# ATX_Power_Breakout_v1p6.net
KiCad netlist of a schematic drawn in EAGLE
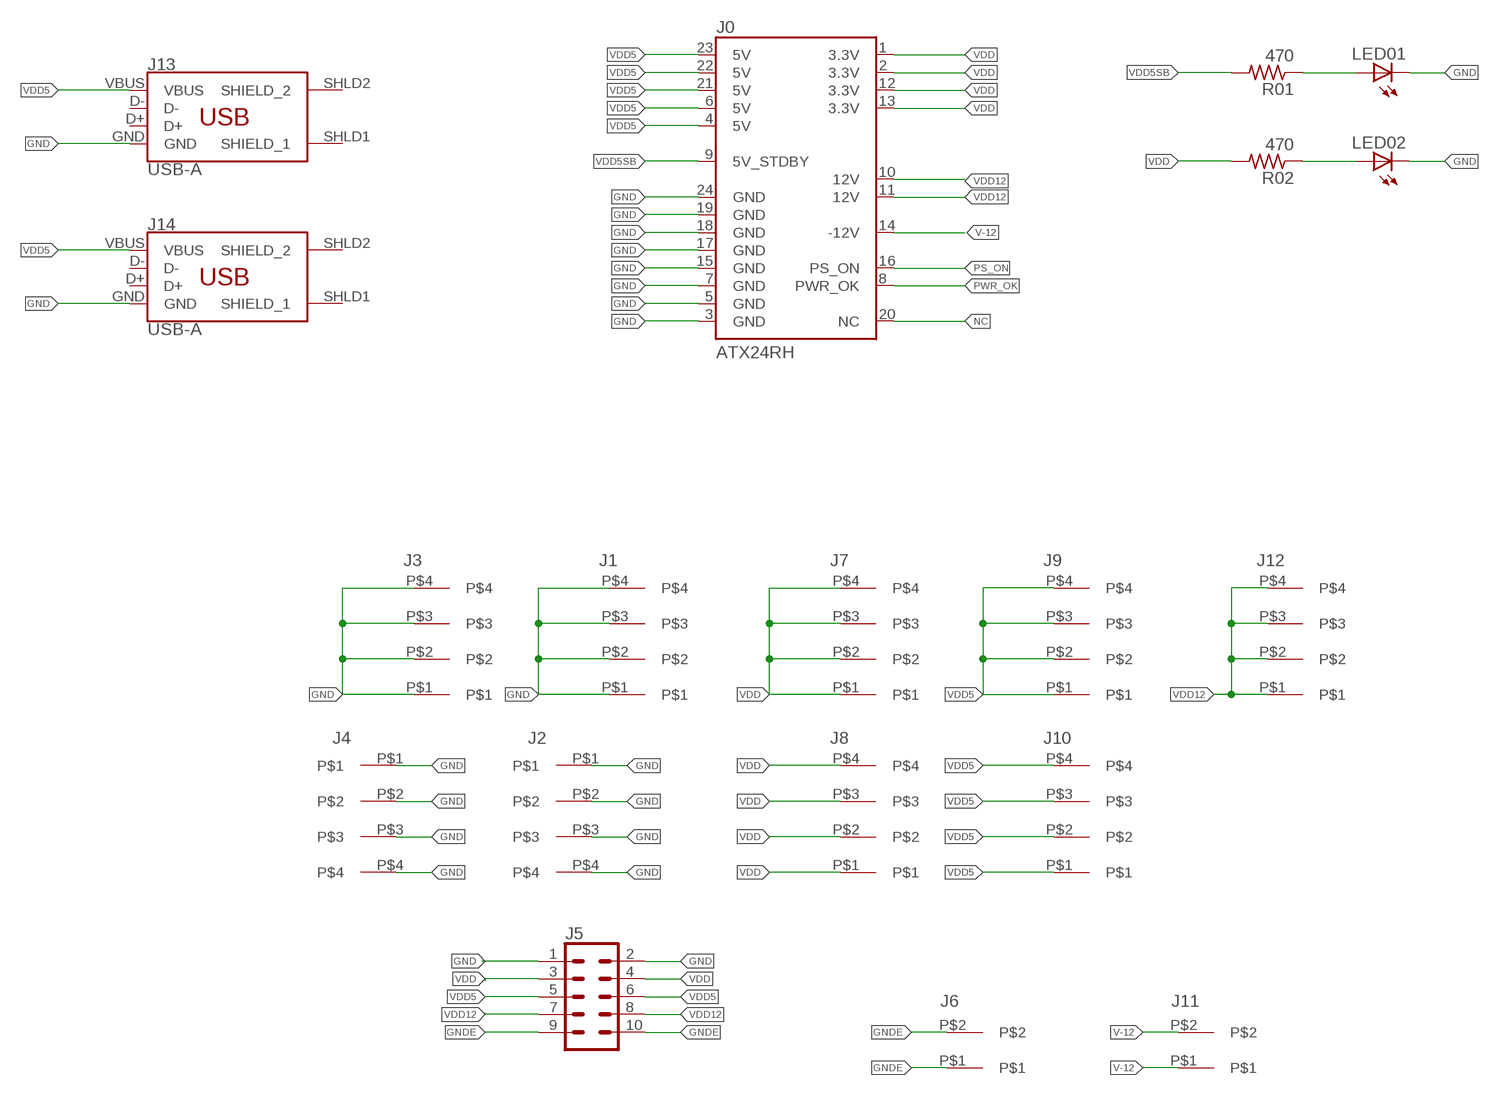
[diagram p0: schematic, sheet 1]

(export (version "E")
  (design (tool "Eeschema 10.0.6"))
  (components
    (comp (ref "J0")
      (value "ATX24RH")
      (footprint "eagle-import:ATX24_RIGHT_ANGLE")
      (libsource (lib "eagle-import") (part "ATX24RH"))
    )
    (comp (ref "J1")
      (value "3.81MM_1_X_4_RT_ANGLE_PLUG_HEADER")
      (footprint "eagle-import:1X4_3.81MM_PITCH")
      (libsource (lib "eagle-import") (part "3.81MM_1_X_4_RT_ANGLE_PLUG_HEADER"))
    )
    (comp (ref "J2")
      (value "3.81MM_1_X_4_RT_ANGLE_PLUG_HEADER")
      (footprint "eagle-import:1X4_3.81MM_PITCH")
      (libsource (lib "eagle-import") (part "3.81MM_1_X_4_RT_ANGLE_PLUG_HEADER"))
    )
    (comp (ref "J3")
      (value "3.81MM_1_X_4_RT_ANGLE_PLUG_HEADER")
      (footprint "eagle-import:1X4_3.81MM_PITCH")
      (libsource (lib "eagle-import") (part "3.81MM_1_X_4_RT_ANGLE_PLUG_HEADER"))
    )
    (comp (ref "J4")
      (value "3.81MM_1_X_4_RT_ANGLE_PLUG_HEADER")
      (footprint "eagle-import:1X4_3.81MM_PITCH")
      (libsource (lib "eagle-import") (part "3.81MM_1_X_4_RT_ANGLE_PLUG_HEADER"))
    )
    (comp (ref "J5")
      (value "CONN_05X2PTH")
      (footprint "eagle-import:2X5")
      (libsource (lib "eagle-import") (part "CONN_05X2PTH"))
    )
    (comp (ref "J6")
      (value "3.81MM_1_X_2_RT_ANGLE_PLUG_HEADER")
      (footprint "eagle-import:2_3.81MM_PITCH")
      (libsource (lib "eagle-import") (part "3.81MM_1_X_2_RT_ANGLE_PLUG_HEADER"))
    )
    (comp (ref "J7")
      (value "3.81MM_1_X_4_RT_ANGLE_PLUG_HEADER")
      (footprint "eagle-import:1X4_3.81MM_PITCH")
      (libsource (lib "eagle-import") (part "3.81MM_1_X_4_RT_ANGLE_PLUG_HEADER"))
    )
    (comp (ref "J8")
      (value "3.81MM_1_X_4_RT_ANGLE_PLUG_HEADER")
      (footprint "eagle-import:1X4_3.81MM_PITCH")
      (libsource (lib "eagle-import") (part "3.81MM_1_X_4_RT_ANGLE_PLUG_HEADER"))
    )
    (comp (ref "J9")
      (value "3.81MM_1_X_4_RT_ANGLE_PLUG_HEADER")
      (footprint "eagle-import:1X4_3.81MM_PITCH")
      (libsource (lib "eagle-import") (part "3.81MM_1_X_4_RT_ANGLE_PLUG_HEADER"))
    )
    (comp (ref "J10")
      (value "3.81MM_1_X_4_RT_ANGLE_PLUG_HEADER")
      (footprint "eagle-import:1X4_3.81MM_PITCH")
      (libsource (lib "eagle-import") (part "3.81MM_1_X_4_RT_ANGLE_PLUG_HEADER"))
    )
    (comp (ref "J11")
      (value "3.81MM_1_X_2_RT_ANGLE_PLUG_HEADER")
      (footprint "eagle-import:2_3.81MM_PITCH")
      (libsource (lib "eagle-import") (part "3.81MM_1_X_2_RT_ANGLE_PLUG_HEADER"))
    )
    (comp (ref "J12")
      (value "3.81MM_1_X_4_RT_ANGLE_PLUG_HEADER")
      (footprint "eagle-import:1X4_3.81MM_PITCH")
      (libsource (lib "eagle-import") (part "3.81MM_1_X_4_RT_ANGLE_PLUG_HEADER"))
    )
    (comp (ref "J13")
      (value "USB-A")
      (footprint "eagle-import:USB_A_SMT")
      (fields (field (name "PARTNO") "87583-3010RPALF"))
      (libsource (lib "eagle-import") (part "USB_A"))
    )
    (comp (ref "J14")
      (value "USB-A")
      (footprint "eagle-import:USB_A_SMT")
      (fields (field (name "PARTNO") "87583-3010RPALF"))
      (libsource (lib "eagle-import") (part "USB_A"))
    )
    (comp (ref "LED01")
      (value "GREEN")
      (footprint "eagle-import:LED_0805_GREEN")
      (libsource (lib "eagle-import") (part "LED_0805_GREEN"))
    )
    (comp (ref "LED02")
      (value "GREEN")
      (footprint "eagle-import:LED_0805_GREEN")
      (libsource (lib "eagle-import") (part "LED_0805_GREEN"))
    )
    (comp (ref "R01")
      (value "470")
      (footprint "eagle-import:0402")
      (libsource (lib "eagle-import") (part "R_0402"))
    )
    (comp (ref "R02")
      (value "470")
      (footprint "eagle-import:0402")
      (libsource (lib "eagle-import") (part "R_0402"))
    )
  )
  (nets
    (net (code "1") (name "GND") (class "Default")
      (node (ref "J0") (pin "15") (pinfunction "GND_15") (pintype "bidirectional"))
      (node (ref "J0") (pin "17") (pinfunction "GND_17") (pintype "bidirectional"))
      (node (ref "J0") (pin "18") (pinfunction "GND_18") (pintype "bidirectional"))
      (node (ref "J0") (pin "19") (pinfunction "GND_19") (pintype "bidirectional"))
      (node (ref "J0") (pin "24") (pinfunction "GND_24") (pintype "bidirectional"))
      (node (ref "J0") (pin "3") (pinfunction "GND_3") (pintype "bidirectional"))
      (node (ref "J0") (pin "5") (pinfunction "GND_5") (pintype "bidirectional"))
      (node (ref "J0") (pin "7") (pinfunction "GND_7") (pintype "bidirectional"))
      (node (ref "J1") (pin "P$1") (pinfunction "P$1_P$1") (pintype "bidirectional"))
      (node (ref "J1") (pin "P$2") (pinfunction "P$2_P$2") (pintype "bidirectional"))
      (node (ref "J1") (pin "P$3") (pinfunction "P$3_P$3") (pintype "bidirectional"))
      (node (ref "J1") (pin "P$4") (pinfunction "P$4_P$4") (pintype "bidirectional"))
      (node (ref "J13") (pin "GND") (pinfunction "GND_GND") (pintype "power_in"))
      (node (ref "J14") (pin "GND") (pinfunction "GND_GND") (pintype "power_in"))
      (node (ref "J2") (pin "P$1") (pinfunction "P$1_P$1") (pintype "bidirectional"))
      (node (ref "J2") (pin "P$2") (pinfunction "P$2_P$2") (pintype "bidirectional"))
      (node (ref "J2") (pin "P$3") (pinfunction "P$3_P$3") (pintype "bidirectional"))
      (node (ref "J2") (pin "P$4") (pinfunction "P$4_P$4") (pintype "bidirectional"))
      (node (ref "J3") (pin "P$1") (pinfunction "P$1_P$1") (pintype "bidirectional"))
      (node (ref "J3") (pin "P$2") (pinfunction "P$2_P$2") (pintype "bidirectional"))
      (node (ref "J3") (pin "P$3") (pinfunction "P$3_P$3") (pintype "bidirectional"))
      (node (ref "J3") (pin "P$4") (pinfunction "P$4_P$4") (pintype "bidirectional"))
      (node (ref "J4") (pin "P$1") (pinfunction "P$1_P$1") (pintype "bidirectional"))
      (node (ref "J4") (pin "P$2") (pinfunction "P$2_P$2") (pintype "bidirectional"))
      (node (ref "J4") (pin "P$3") (pinfunction "P$3_P$3") (pintype "bidirectional"))
      (node (ref "J4") (pin "P$4") (pinfunction "P$4_P$4") (pintype "bidirectional"))
      (node (ref "J5") (pin "1") (pinfunction "1_1") (pintype "passive"))
      (node (ref "J5") (pin "2") (pinfunction "2_2") (pintype "passive"))
      (node (ref "LED01") (pin "C") (pinfunction "C_C") (pintype "passive"))
      (node (ref "LED02") (pin "C") (pinfunction "C_C") (pintype "passive"))
    )
    (net (code "2") (name "GNDE") (class "Default")
      (node (ref "J5") (pin "10") (pinfunction "10_10") (pintype "passive"))
      (node (ref "J5") (pin "9") (pinfunction "9_9") (pintype "passive"))
      (node (ref "J6") (pin "P$1") (pinfunction "P$1_P$1") (pintype "bidirectional"))
      (node (ref "J6") (pin "P$2") (pinfunction "P$2_P$2") (pintype "bidirectional"))
    )
    (net (code "3") (name "NC") (class "Default")
      (node (ref "J0") (pin "20") (pinfunction "NC_20") (pintype "bidirectional"))
    )
    (net (code "4") (name "Net-(R01-1)") (class "Default")
      (node (ref "LED01") (pin "A") (pinfunction "A_A") (pintype "passive"))
      (node (ref "R01") (pin "P$1") (pinfunction "1_P$1") (pintype "passive"))
    )
    (net (code "5") (name "Net-(R02-1)") (class "Default")
      (node (ref "LED02") (pin "A") (pinfunction "A_A") (pintype "passive"))
      (node (ref "R02") (pin "P$1") (pinfunction "1_P$1") (pintype "passive"))
    )
    (net (code "6") (name "PS_ON") (class "Default")
      (node (ref "J0") (pin "16") (pinfunction "PS_ON_16") (pintype "bidirectional"))
    )
    (net (code "7") (name "PWR_OK") (class "Default")
      (node (ref "J0") (pin "8") (pinfunction "PWR_OK_8") (pintype "bidirectional"))
    )
    (net (code "8") (name "V-12") (class "Default")
      (node (ref "J0") (pin "14") (pinfunction "-12V_14") (pintype "bidirectional"))
      (node (ref "J11") (pin "P$1") (pinfunction "P$1_P$1") (pintype "bidirectional"))
      (node (ref "J11") (pin "P$2") (pinfunction "P$2_P$2") (pintype "bidirectional"))
    )
    (net (code "9") (name "VDD") (class "Default")
      (node (ref "J0") (pin "1") (pinfunction "3.3V_1") (pintype "bidirectional"))
      (node (ref "J0") (pin "12") (pinfunction "3.3V_12") (pintype "bidirectional"))
      (node (ref "J0") (pin "13") (pinfunction "3.3V_13") (pintype "bidirectional"))
      (node (ref "J0") (pin "2") (pinfunction "3.3V_2") (pintype "bidirectional"))
      (node (ref "J5") (pin "3") (pinfunction "3_3") (pintype "passive"))
      (node (ref "J5") (pin "4") (pinfunction "4_4") (pintype "passive"))
      (node (ref "J7") (pin "P$1") (pinfunction "P$1_P$1") (pintype "bidirectional"))
      (node (ref "J7") (pin "P$2") (pinfunction "P$2_P$2") (pintype "bidirectional"))
      (node (ref "J7") (pin "P$3") (pinfunction "P$3_P$3") (pintype "bidirectional"))
      (node (ref "J7") (pin "P$4") (pinfunction "P$4_P$4") (pintype "bidirectional"))
      (node (ref "J8") (pin "P$1") (pinfunction "P$1_P$1") (pintype "bidirectional"))
      (node (ref "J8") (pin "P$2") (pinfunction "P$2_P$2") (pintype "bidirectional"))
      (node (ref "J8") (pin "P$3") (pinfunction "P$3_P$3") (pintype "bidirectional"))
      (node (ref "J8") (pin "P$4") (pinfunction "P$4_P$4") (pintype "bidirectional"))
      (node (ref "R02") (pin "P$2") (pinfunction "2_P$2") (pintype "passive"))
    )
    (net (code "10") (name "VDD5") (class "Default")
      (node (ref "J0") (pin "21") (pinfunction "5V_21") (pintype "bidirectional"))
      (node (ref "J0") (pin "22") (pinfunction "5V_22") (pintype "bidirectional"))
      (node (ref "J0") (pin "23") (pinfunction "5V_23") (pintype "bidirectional"))
      (node (ref "J0") (pin "4") (pinfunction "5V_4") (pintype "bidirectional"))
      (node (ref "J0") (pin "6") (pinfunction "5V_6") (pintype "bidirectional"))
      (node (ref "J10") (pin "P$1") (pinfunction "P$1_P$1") (pintype "bidirectional"))
      (node (ref "J10") (pin "P$2") (pinfunction "P$2_P$2") (pintype "bidirectional"))
      (node (ref "J10") (pin "P$3") (pinfunction "P$3_P$3") (pintype "bidirectional"))
      (node (ref "J10") (pin "P$4") (pinfunction "P$4_P$4") (pintype "bidirectional"))
      (node (ref "J13") (pin "VBUS") (pinfunction "VBUS_VBUS") (pintype "power_in"))
      (node (ref "J14") (pin "VBUS") (pinfunction "VBUS_VBUS") (pintype "power_in"))
      (node (ref "J5") (pin "5") (pinfunction "5_5") (pintype "passive"))
      (node (ref "J5") (pin "6") (pinfunction "6_6") (pintype "passive"))
      (node (ref "J9") (pin "P$1") (pinfunction "P$1_P$1") (pintype "bidirectional"))
      (node (ref "J9") (pin "P$2") (pinfunction "P$2_P$2") (pintype "bidirectional"))
      (node (ref "J9") (pin "P$3") (pinfunction "P$3_P$3") (pintype "bidirectional"))
      (node (ref "J9") (pin "P$4") (pinfunction "P$4_P$4") (pintype "bidirectional"))
    )
    (net (code "11") (name "VDD5SB") (class "Default")
      (node (ref "J0") (pin "9") (pinfunction "5V_STDBY_9") (pintype "bidirectional"))
      (node (ref "R01") (pin "P$2") (pinfunction "2_P$2") (pintype "passive"))
    )
    (net (code "12") (name "VDD12") (class "Default")
      (node (ref "J0") (pin "10") (pinfunction "12V_10") (pintype "bidirectional"))
      (node (ref "J0") (pin "11") (pinfunction "12V_11") (pintype "bidirectional"))
      (node (ref "J12") (pin "P$1") (pinfunction "P$1_P$1") (pintype "bidirectional"))
      (node (ref "J12") (pin "P$2") (pinfunction "P$2_P$2") (pintype "bidirectional"))
      (node (ref "J12") (pin "P$3") (pinfunction "P$3_P$3") (pintype "bidirectional"))
      (node (ref "J12") (pin "P$4") (pinfunction "P$4_P$4") (pintype "bidirectional"))
      (node (ref "J5") (pin "7") (pinfunction "7_7") (pintype "passive"))
      (node (ref "J5") (pin "8") (pinfunction "8_8") (pintype "passive"))
    )
    (net (code "13") (name "unconnected-(J13-PadD+)") (class "Default")
      (node (ref "J13") (pin "D+") (pinfunction "D+_D+") (pintype "bidirectional"))
    )
    (net (code "14") (name "unconnected-(J13-PadD-)") (class "Default")
      (node (ref "J13") (pin "D-") (pinfunction "D-_D-") (pintype "bidirectional"))
    )
    (net (code "15") (name "unconnected-(J13-SHIELD_1-PadSHLD1)") (class "Default")
      (node (ref "J13") (pin "SHLD1") (pinfunction "SHIELD_1_SHLD1") (pintype "bidirectional"))
    )
    (net (code "16") (name "unconnected-(J13-SHIELD_2-PadSHLD2)") (class "Default")
      (node (ref "J13") (pin "SHLD2") (pinfunction "SHIELD_2_SHLD2") (pintype "bidirectional"))
    )
    (net (code "17") (name "unconnected-(J14-PadD+)") (class "Default")
      (node (ref "J14") (pin "D+") (pinfunction "D+_D+") (pintype "bidirectional"))
    )
    (net (code "18") (name "unconnected-(J14-PadD-)") (class "Default")
      (node (ref "J14") (pin "D-") (pinfunction "D-_D-") (pintype "bidirectional"))
    )
    (net (code "19") (name "unconnected-(J14-SHIELD_1-PadSHLD1)") (class "Default")
      (node (ref "J14") (pin "SHLD1") (pinfunction "SHIELD_1_SHLD1") (pintype "bidirectional"))
    )
    (net (code "20") (name "unconnected-(J14-SHIELD_2-PadSHLD2)") (class "Default")
      (node (ref "J14") (pin "SHLD2") (pinfunction "SHIELD_2_SHLD2") (pintype "bidirectional"))
    )
  )
)
